# Ardiboard.net
KiCad netlist of a schematic drawn in EAGLE
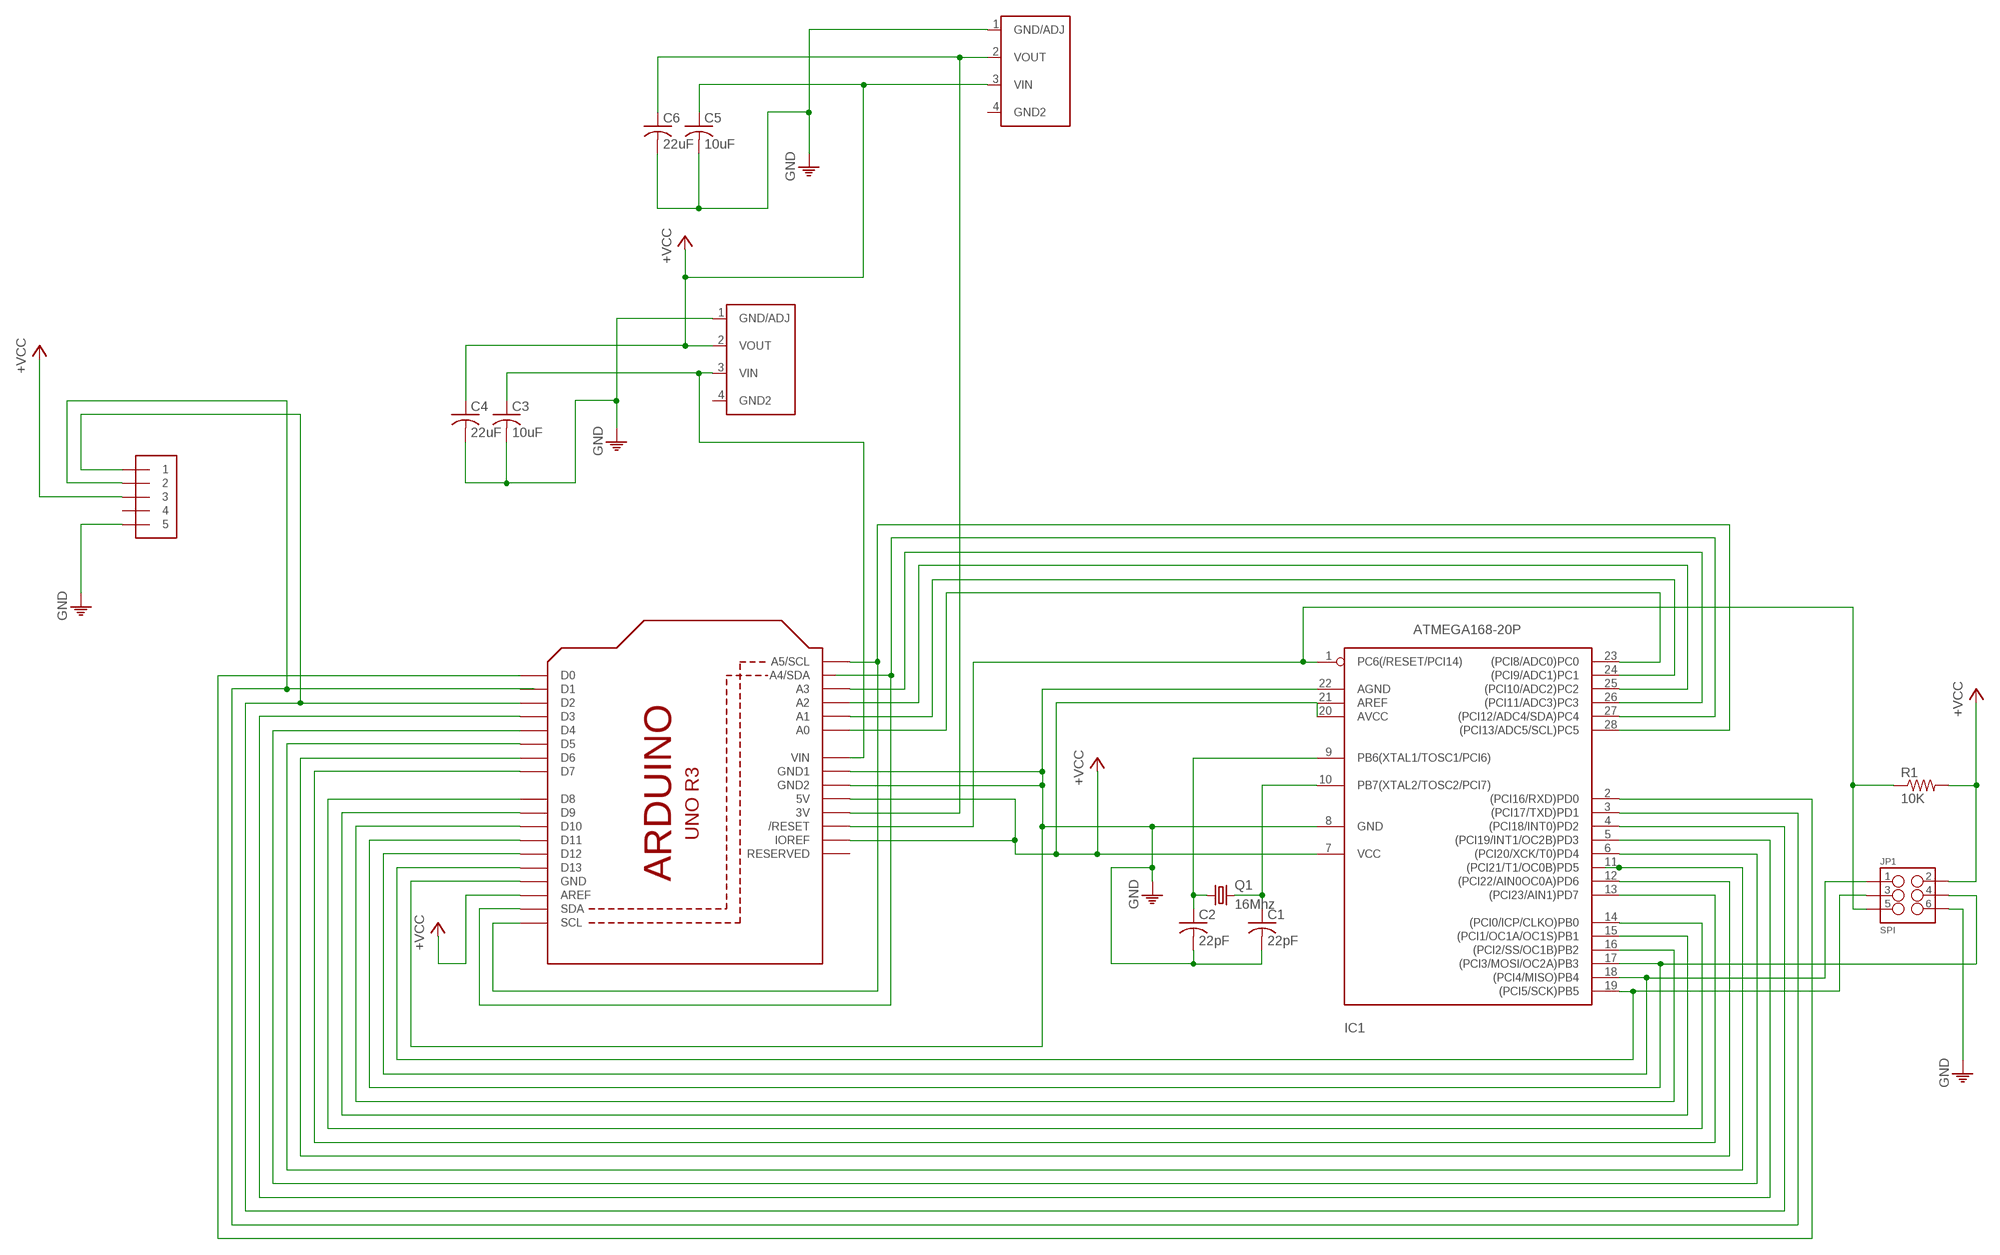
[diagram p0: schematic, sheet 1]

(export (version "E")
  (design (tool "Eeschema 10.0.6"))
  (components
    (comp (ref "C1")
      (value "22pF")
      (footprint "eagle-import:C025-025X050")
      (libsource (lib "eagle-import") (part "C-US025-025X050"))
    )
    (comp (ref "C2")
      (value "22pF")
      (footprint "eagle-import:C025-025X050")
      (libsource (lib "eagle-import") (part "C-US025-025X050"))
    )
    (comp (ref "C3")
      (value "10uF")
      (footprint "eagle-import:C025-030X050")
      (libsource (lib "eagle-import") (part "C-US025-030X050"))
    )
    (comp (ref "C4")
      (value "22uF")
      (footprint "eagle-import:C025-030X050")
      (libsource (lib "eagle-import") (part "C-US025-030X050"))
    )
    (comp (ref "C5")
      (value "10uF")
      (footprint "eagle-import:C025-030X050")
      (libsource (lib "eagle-import") (part "C-US025-030X050"))
    )
    (comp (ref "C6")
      (value "22uF")
      (footprint "eagle-import:C025-030X050")
      (libsource (lib "eagle-import") (part "C-US025-030X050"))
    )
    (comp (ref "IC1")
      (value "ATMEGA168-20P")
      (footprint "eagle-import:DIL28-3")
      (libsource (lib "eagle-import") (part "ATMEGA168P-20"))
    )
    (comp (ref "J1")
      (value "1X5")
      (footprint "eagle-import:1X05-3.5MM")
      (libsource (lib "eagle-import") (part "1X5"))
    )
    (comp (ref "JP1")
      (value "SPI")
      (footprint "eagle-import:2X3-SHROUDED")
      (libsource (lib "eagle-import") (part "M03X2"))
    )
    (comp (ref "Q1")
      (value "16Mhz")
      (footprint "eagle-import:HC49_S")
      (libsource (lib "eagle-import") (part "CRYSTALHC49S"))
    )
    (comp (ref "Q2")
      (value "AZ1086H-5.0")
      (footprint "eagle-import:SOT223")
      (libsource (lib "eagle-import") (part "AZ1086-XX"))
    )
    (comp (ref "Q3")
      (value "AZ1086H-3.3")
      (footprint "eagle-import:SOT223")
      (libsource (lib "eagle-import") (part "AZ1086-XX"))
    )
    (comp (ref "R1")
      (value "10K")
      (footprint "eagle-import:0207_10")
      (libsource (lib "eagle-import") (part "R-US_0207/10"))
    )
    (comp (ref "U1")
      (value "ARDUINOR3-BPLACE")
      (footprint "eagle-import:ARDUINOR3-BPLACE")
      (libsource (lib "eagle-import") (part "ARDUINOR3-BPLACE"))
    )
  )
  (nets
    (net (code "1") (name "+VCC") (class "Default")
      (node (ref "C4") (pin "1") (pinfunction "1_1") (pintype "passive"))
      (node (ref "C5") (pin "1") (pinfunction "1_1") (pintype "passive"))
      (node (ref "IC1") (pin "20") (pinfunction "AVCC_20") (pintype "bidirectional"))
      (node (ref "IC1") (pin "21") (pinfunction "AREF_21") (pintype "bidirectional"))
      (node (ref "IC1") (pin "7") (pinfunction "VCC_7") (pintype "bidirectional"))
      (node (ref "J1") (pin "3") (pinfunction "3_3") (pintype "passive"))
      (node (ref "JP1") (pin "2") (pinfunction "2_2") (pintype "bidirectional"))
      (node (ref "Q2") (pin "2") (pinfunction "VOUT_2") (pintype "bidirectional"))
      (node (ref "Q3") (pin "3") (pinfunction "VIN_3") (pintype "bidirectional"))
      (node (ref "R1") (pin "2") (pinfunction "2_2") (pintype "passive"))
      (node (ref "U1") (pin "5V") (pinfunction "5V_5V") (pintype "power_in"))
      (node (ref "U1") (pin "AREF") (pinfunction "AREF_AREF") (pintype "bidirectional"))
      (node (ref "U1") (pin "IOREF") (pinfunction "IOREF_IOREF") (pintype "output"))
    )
    (net (code "2") (name "GND") (class "Default")
      (node (ref "C1") (pin "2") (pinfunction "2_2") (pintype "passive"))
      (node (ref "C2") (pin "2") (pinfunction "2_2") (pintype "passive"))
      (node (ref "C3") (pin "2") (pinfunction "2_2") (pintype "passive"))
      (node (ref "C4") (pin "2") (pinfunction "2_2") (pintype "passive"))
      (node (ref "C5") (pin "2") (pinfunction "2_2") (pintype "passive"))
      (node (ref "C6") (pin "2") (pinfunction "2_2") (pintype "passive"))
      (node (ref "IC1") (pin "22") (pinfunction "AGND_22") (pintype "bidirectional"))
      (node (ref "IC1") (pin "8") (pinfunction "GND_8") (pintype "bidirectional"))
      (node (ref "J1") (pin "5") (pinfunction "5_5") (pintype "passive"))
      (node (ref "JP1") (pin "6") (pinfunction "6_6") (pintype "bidirectional"))
      (node (ref "Q2") (pin "1") (pinfunction "GND/ADJ_1") (pintype "bidirectional"))
      (node (ref "Q3") (pin "1") (pinfunction "GND/ADJ_1") (pintype "bidirectional"))
      (node (ref "U1") (pin "GND") (pinfunction "GND_GND") (pintype "power_in"))
      (node (ref "U1") (pin "GND1") (pinfunction "GND1_GND1") (pintype "power_in"))
      (node (ref "U1") (pin "GND2") (pinfunction "GND2_GND2") (pintype "power_in"))
    )
    (net (code "3") (name "Net-(IC1-(PCI0{slash}ICP{slash}CLKO)PB0)") (class "Default")
      (node (ref "IC1") (pin "14") (pinfunction "(PCI0/ICP/CLKO)PB0_14") (pintype "bidirectional"))
      (node (ref "U1") (pin "D8") (pinfunction "D8_D8") (pintype "bidirectional"))
    )
    (net (code "4") (name "Net-(IC1-(PCI1{slash}OC1A{slash}OC1S)PB1)") (class "Default")
      (node (ref "IC1") (pin "15") (pinfunction "(PCI1/OC1A/OC1S)PB1_15") (pintype "bidirectional"))
      (node (ref "U1") (pin "D9") (pinfunction "D9_D9") (pintype "bidirectional"))
    )
    (net (code "5") (name "Net-(IC1-(PCI2{slash}SS{slash}OC1B)PB2)") (class "Default")
      (node (ref "IC1") (pin "16") (pinfunction "(PCI2/SS/OC1B)PB2_16") (pintype "bidirectional"))
      (node (ref "U1") (pin "D10") (pinfunction "D10_D10") (pintype "bidirectional"))
    )
    (net (code "6") (name "Net-(IC1-(PCI3{slash}MOSI{slash}OC2A)PB3)") (class "Default")
      (node (ref "IC1") (pin "17") (pinfunction "(PCI3/MOSI/OC2A)PB3_17") (pintype "bidirectional"))
      (node (ref "JP1") (pin "4") (pinfunction "4_4") (pintype "bidirectional"))
      (node (ref "U1") (pin "D11") (pinfunction "D11_D11") (pintype "bidirectional"))
    )
    (net (code "7") (name "Net-(IC1-(PCI4{slash}MISO)PB4)") (class "Default")
      (node (ref "IC1") (pin "18") (pinfunction "(PCI4/MISO)PB4_18") (pintype "bidirectional"))
      (node (ref "JP1") (pin "1") (pinfunction "1_1") (pintype "bidirectional"))
      (node (ref "U1") (pin "D12") (pinfunction "D12_D12") (pintype "bidirectional"))
    )
    (net (code "8") (name "Net-(IC1-(PCI5{slash}SCK)PB5)") (class "Default")
      (node (ref "IC1") (pin "19") (pinfunction "(PCI5/SCK)PB5_19") (pintype "bidirectional"))
      (node (ref "JP1") (pin "3") (pinfunction "3_3") (pintype "bidirectional"))
      (node (ref "U1") (pin "D13") (pinfunction "D13_D13") (pintype "bidirectional"))
    )
    (net (code "9") (name "Net-(IC1-(PCI8{slash}ADC0)PC0)") (class "Default")
      (node (ref "IC1") (pin "23") (pinfunction "(PCI8/ADC0)PC0_23") (pintype "bidirectional"))
      (node (ref "U1") (pin "A0") (pinfunction "A0_A0") (pintype "bidirectional"))
    )
    (net (code "10") (name "Net-(IC1-(PCI9{slash}ADC1)PC1)") (class "Default")
      (node (ref "IC1") (pin "24") (pinfunction "(PCI9/ADC1)PC1_24") (pintype "bidirectional"))
      (node (ref "U1") (pin "A1") (pinfunction "A1_A1") (pintype "bidirectional"))
    )
    (net (code "11") (name "Net-(IC1-(PCI10{slash}ADC2)PC2)") (class "Default")
      (node (ref "IC1") (pin "25") (pinfunction "(PCI10/ADC2)PC2_25") (pintype "bidirectional"))
      (node (ref "U1") (pin "A2") (pinfunction "A2_A2") (pintype "bidirectional"))
    )
    (net (code "12") (name "Net-(IC1-(PCI11{slash}ADC3)PC3)") (class "Default")
      (node (ref "IC1") (pin "26") (pinfunction "(PCI11/ADC3)PC3_26") (pintype "bidirectional"))
      (node (ref "U1") (pin "A3") (pinfunction "A3_A3") (pintype "bidirectional"))
    )
    (net (code "13") (name "Net-(IC1-(PCI12{slash}ADC4{slash}SDA)PC4)") (class "Default")
      (node (ref "IC1") (pin "27") (pinfunction "(PCI12/ADC4/SDA)PC4_27") (pintype "bidirectional"))
      (node (ref "U1") (pin "SDA") (pinfunction "SDA_SDA") (pintype "bidirectional"))
    )
    (net (code "14") (name "Net-(IC1-(PCI13{slash}ADC5{slash}SCL)PC5)") (class "Default")
      (node (ref "IC1") (pin "28") (pinfunction "(PCI13/ADC5/SCL)PC5_28") (pintype "bidirectional"))
      (node (ref "U1") (pin "A5") (pinfunction "A5/SCL_A5") (pintype "bidirectional"))
      (node (ref "U1") (pin "SCL") (pinfunction "SCL_SCL") (pintype "bidirectional"))
    )
    (net (code "15") (name "Net-(IC1-(PCI16{slash}RXD)PD0)") (class "Default")
      (node (ref "IC1") (pin "2") (pinfunction "(PCI16/RXD)PD0_2") (pintype "bidirectional"))
      (node (ref "U1") (pin "D0") (pinfunction "D0_D0") (pintype "bidirectional"))
    )
    (net (code "16") (name "Net-(IC1-(PCI17{slash}TXD)PD1)") (class "Default")
      (node (ref "IC1") (pin "3") (pinfunction "(PCI17/TXD)PD1_3") (pintype "bidirectional"))
      (node (ref "J1") (pin "2") (pinfunction "2_2") (pintype "passive"))
    )
    (net (code "17") (name "Net-(IC1-(PCI18{slash}INT0)PD2)") (class "Default")
      (node (ref "IC1") (pin "4") (pinfunction "(PCI18/INT0)PD2_4") (pintype "bidirectional"))
      (node (ref "J1") (pin "1") (pinfunction "1_1") (pintype "passive"))
      (node (ref "U1") (pin "D2") (pinfunction "D2_D2") (pintype "bidirectional"))
    )
    (net (code "18") (name "Net-(IC1-(PCI19{slash}INT1{slash}OC2B)PD3)") (class "Default")
      (node (ref "IC1") (pin "5") (pinfunction "(PCI19/INT1/OC2B)PD3_5") (pintype "bidirectional"))
      (node (ref "U1") (pin "D3") (pinfunction "D3_D3") (pintype "bidirectional"))
    )
    (net (code "19") (name "Net-(IC1-(PCI20{slash}XCK{slash}T0)PD4)") (class "Default")
      (node (ref "IC1") (pin "6") (pinfunction "(PCI20/XCK/T0)PD4_6") (pintype "bidirectional"))
      (node (ref "U1") (pin "D4") (pinfunction "D4_D4") (pintype "bidirectional"))
    )
    (net (code "20") (name "Net-(IC1-(PCI21{slash}T1{slash}OC0B)PD5)") (class "Default")
      (node (ref "IC1") (pin "11") (pinfunction "(PCI21/T1/OC0B)PD5_11") (pintype "bidirectional"))
      (node (ref "U1") (pin "D5") (pinfunction "D5_D5") (pintype "bidirectional"))
    )
    (net (code "21") (name "Net-(IC1-(PCI22{slash}AIN0OC0A)PD6)") (class "Default")
      (node (ref "IC1") (pin "12") (pinfunction "(PCI22/AIN0OC0A)PD6_12") (pintype "bidirectional"))
      (node (ref "U1") (pin "D6") (pinfunction "D6_D6") (pintype "bidirectional"))
    )
    (net (code "22") (name "Net-(IC1-(PCI23{slash}AIN1)PD7)") (class "Default")
      (node (ref "IC1") (pin "13") (pinfunction "(PCI23/AIN1)PD7_13") (pintype "bidirectional"))
      (node (ref "U1") (pin "D7") (pinfunction "D7_D7") (pintype "bidirectional"))
    )
    (net (code "23") (name "Net-(IC1-PB6(XTAL1{slash}TOSC1{slash}PCI6))") (class "Default")
      (node (ref "C2") (pin "1") (pinfunction "1_1") (pintype "passive"))
      (node (ref "IC1") (pin "9") (pinfunction "PB6(XTAL1/TOSC1/PCI6)_9") (pintype "bidirectional"))
      (node (ref "Q1") (pin "1") (pinfunction "1_1") (pintype "passive"))
    )
    (net (code "24") (name "Net-(IC1-PB7(XTAL2{slash}TOSC2{slash}PCI7))") (class "Default")
      (node (ref "C1") (pin "1") (pinfunction "1_1") (pintype "passive"))
      (node (ref "IC1") (pin "10") (pinfunction "PB7(XTAL2/TOSC2/PCI7)_10") (pintype "bidirectional"))
      (node (ref "Q1") (pin "2") (pinfunction "2_2") (pintype "passive"))
    )
    (net (code "25") (name "Net-(IC1-PC6({slash}RESET{slash}PCI14))") (class "Default")
      (node (ref "IC1") (pin "1") (pinfunction "PC6(/RESET/PCI14)_1") (pintype "bidirectional"))
      (node (ref "JP1") (pin "5") (pinfunction "5_5") (pintype "bidirectional"))
      (node (ref "R1") (pin "1") (pinfunction "1_1") (pintype "passive"))
      (node (ref "U1") (pin "RESET") (pinfunction "/RESET_RESET") (pintype "bidirectional"))
    )
    (net (code "26") (name "Net-(Q2-VIN)") (class "Default")
      (node (ref "C3") (pin "1") (pinfunction "1_1") (pintype "passive"))
      (node (ref "Q2") (pin "3") (pinfunction "VIN_3") (pintype "bidirectional"))
      (node (ref "U1") (pin "VIN") (pinfunction "VIN_VIN") (pintype "power_in"))
    )
    (net (code "27") (name "Net-(Q3-VOUT)") (class "Default")
      (node (ref "C6") (pin "1") (pinfunction "1_1") (pintype "passive"))
      (node (ref "Q3") (pin "2") (pinfunction "VOUT_2") (pintype "bidirectional"))
      (node (ref "U1") (pin "3V") (pinfunction "3V_3V") (pintype "power_in"))
    )
    (net (code "28") (name "unconnected-(J1-Pad4)") (class "Default")
      (node (ref "J1") (pin "4") (pinfunction "4_4") (pintype "passive"))
    )
    (net (code "29") (name "unconnected-(Q2-GND2-Pad4)") (class "Default")
      (node (ref "Q2") (pin "4") (pinfunction "GND2_4") (pintype "no_connect"))
    )
    (net (code "30") (name "unconnected-(Q3-GND2-Pad4)") (class "Default")
      (node (ref "Q3") (pin "4") (pinfunction "GND2_4") (pintype "no_connect"))
    )
    (net (code "31") (name "unconnected-(U1-A4{slash}SDA-PadA4)") (class "Default")
      (node (ref "U1") (pin "A4") (pinfunction "A4/SDA_A4") (pintype "bidirectional"))
    )
    (net (code "32") (name "unconnected-(U1-PadD1)") (class "Default")
      (node (ref "U1") (pin "D1") (pinfunction "D1_D1") (pintype "bidirectional"))
    )
    (net (code "33") (name "unconnected-(U1-PadRESERVED)") (class "Default")
      (node (ref "U1") (pin "RESERVED") (pinfunction "RESERVED_RESERVED") (pintype "no_connect"))
    )
  )
)
